# P03_Power.net
KiCad netlist of a schematic drawn in Altium Designer
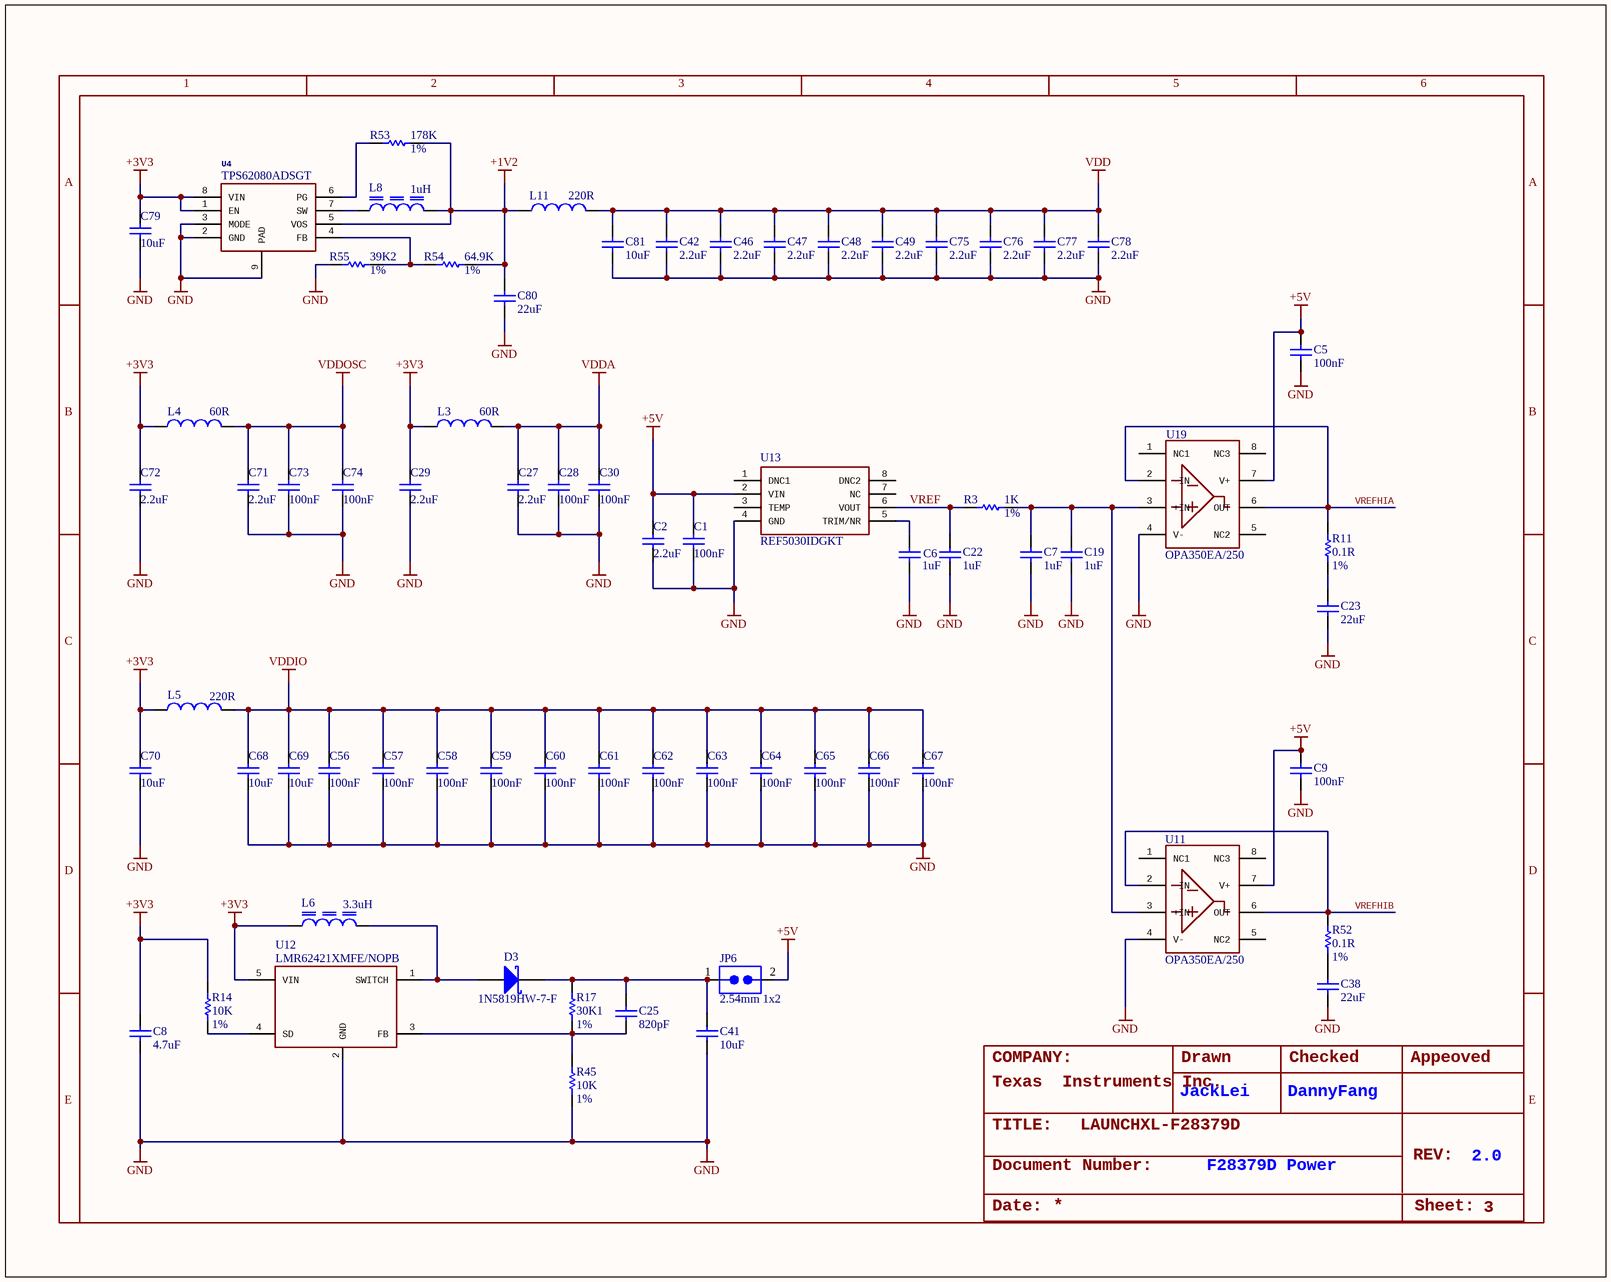
[diagram p0: P03_Power.SchDoc]

(export (version "E")
  (design (tool "Eeschema 10.0.6"))
  (components
    (comp (ref "C1")
      (value "100nF")
      (footprint "C0402")
      (description "CAP,100NF(0.1uf),+/-10%,X5R,10V,SMD0402")
      (fields
        (field (name "MANUFACTURER") "MURATA")
        (field (name "MANUFACTURER PART NUMBER") "GRM155R61A104KA01D")
      )
      (libsource (lib "Embest") (part "C"))
    )
    (comp (ref "C2")
      (value "2.2uF")
      (footprint "C0402")
      (description "CAP,2.2UF,+/-20%,X5R,6.3V,SMD0402")
      (fields
        (field (name "MANUFACTURER") "MURATA")
        (field (name "MANUFACTURER PART NUMBER") "GRM155R60J225ME15D")
      )
      (libsource (lib "Embest") (part "C"))
    )
    (comp (ref "C5")
      (value "100nF")
      (footprint "C0402")
      (description "CAP,100NF(0.1uf),+/-10%,X5R,10V,SMD0402")
      (fields
        (field (name "MANUFACTURER") "MURATA")
        (field (name "MANUFACTURER PART NUMBER") "GRM155R61A104KA01D")
      )
      (libsource (lib "Embest") (part "C"))
    )
    (comp (ref "C6")
      (value "1uF")
      (footprint "C0402")
      (description "CAP,1UF,+/-10%,X5R,6.3V,SMD0402")
      (fields
        (field (name "MANUFACTURER") "MURATA")
        (field (name "MANUFACTURER PART NUMBER") "GRM155R60J105KE19D")
      )
      (libsource (lib "Embest") (part "C"))
    )
    (comp (ref "C7")
      (value "1uF")
      (footprint "C0402")
      (description "CAP,1UF,+/-10%,X5R,6.3V,SMD0402")
      (fields
        (field (name "MANUFACTURER") "MURATA")
        (field (name "MANUFACTURER PART NUMBER") "GRM155R60J105KE19D")
      )
      (libsource (lib "Embest") (part "C"))
    )
    (comp (ref "C8")
      (value "4.7uF")
      (footprint "C0402")
      (description "CAP,4.7UF,+/-20%,X5R,6.3V,SMD0402 fix PN add D（20151023）")
      (fields
        (field (name "MANUFACTURER") "MURATA")
        (field (name "MANUFACTURER PART NUMBER") "GRM155R60J475ME47D")
      )
      (libsource (lib "Embest") (part "C"))
    )
    (comp (ref "C9")
      (value "100nF")
      (footprint "C0402")
      (description "CAP,100NF(0.1uf),+/-10%,X5R,10V,SMD0402")
      (fields
        (field (name "MANUFACTURER") "MURATA")
        (field (name "MANUFACTURER PART NUMBER") "GRM155R61A104KA01D")
      )
      (libsource (lib "Embest") (part "C"))
    )
    (comp (ref "C19")
      (value "1uF")
      (footprint "C0402")
      (description "CAP,1UF,+/-10%,X5R,6.3V,SMD0402")
      (fields
        (field (name "MANUFACTURER") "MURATA")
        (field (name "MANUFACTURER PART NUMBER") "GRM155R60J105KE19D")
      )
      (libsource (lib "Embest") (part "C"))
    )
    (comp (ref "C22")
      (value "1uF")
      (footprint "C0402")
      (description "CAP,1UF,+/-10%,X5R,6.3V,SMD0402")
      (fields
        (field (name "MANUFACTURER") "MURATA")
        (field (name "MANUFACTURER PART NUMBER") "GRM155R60J105KE19D")
      )
      (libsource (lib "Embest") (part "C"))
    )
    (comp (ref "C23")
      (value "22uF")
      (footprint "C0603")
      (description "CAP,22UF,+/-20%,X5R,6.3V,SMD0603")
      (fields
        (field (name "MANUFACTURER") "MURATA")
        (field (name "MANUFACTURER PART NUMBER") "GRM188R60J226MEA0D")
      )
      (libsource (lib "Embest") (part "C"))
    )
    (comp (ref "C25")
      (value "820pF")
      (footprint "C0402")
      (description "CAP,820PF,+/-5%,C0G,50V,SMD0402")
      (fields
        (field (name "MANUFACTURER") "MURATA")
        (field (name "MANUFACTURER PART NUMBER") "GRM1555C1H821JA01D")
      )
      (libsource (lib "Embest") (part "C"))
    )
    (comp (ref "C27")
      (value "2.2uF")
      (footprint "C0402")
      (description "CAP,2.2UF,+/-20%,X5R,6.3V,SMD0402")
      (fields
        (field (name "MANUFACTURER") "MURATA")
        (field (name "MANUFACTURER PART NUMBER") "GRM155R60J225ME15D")
      )
      (libsource (lib "Embest") (part "C"))
    )
    (comp (ref "C28")
      (value "100nF")
      (footprint "C0402")
      (description "CAP,100NF(0.1uf),+/-10%,X5R,10V,SMD0402")
      (fields
        (field (name "MANUFACTURER") "MURATA")
        (field (name "MANUFACTURER PART NUMBER") "GRM155R61A104KA01D")
      )
      (libsource (lib "Embest") (part "C"))
    )
    (comp (ref "C29")
      (value "2.2uF")
      (footprint "C0402")
      (description "CAP,2.2UF,+/-20%,X5R,6.3V,SMD0402")
      (fields
        (field (name "MANUFACTURER") "MURATA")
        (field (name "MANUFACTURER PART NUMBER") "GRM155R60J225ME15D")
      )
      (libsource (lib "Embest") (part "C"))
    )
    (comp (ref "C30")
      (value "100nF")
      (footprint "C0402")
      (description "CAP,100NF(0.1uf),+/-10%,X5R,10V,SMD0402")
      (fields
        (field (name "MANUFACTURER") "MURATA")
        (field (name "MANUFACTURER PART NUMBER") "GRM155R61A104KA01D")
      )
      (libsource (lib "Embest") (part "C"))
    )
    (comp (ref "C38")
      (value "22uF")
      (footprint "C0603")
      (description "CAP,22UF,+/-20%,X5R,6.3V,SMD0603")
      (fields
        (field (name "MANUFACTURER") "MURATA")
        (field (name "MANUFACTURER PART NUMBER") "GRM188R60J226MEA0D")
      )
      (libsource (lib "Embest") (part "C"))
    )
    (comp (ref "C41")
      (value "10uF")
      (footprint "C1210")
      (description "CAP,10UF,+/-10%,X7R,25V,SMD1210")
      (fields
        (field (name "MANUFACTURER") "MURATA")
        (field (name "MANUFACTURER PART NUMBER") "GRM32DR71E106KA12L")
      )
      (libsource (lib "Embest") (part "C"))
    )
    (comp (ref "C42")
      (value "2.2uF")
      (footprint "C0402")
      (description "CAP,2.2UF,+/-20%,X5R,6.3V,SMD0402")
      (fields
        (field (name "MANUFACTURER") "MURATA")
        (field (name "MANUFACTURER PART NUMBER") "GRM155R60J225ME15D")
      )
      (libsource (lib "Embest") (part "C"))
    )
    (comp (ref "C46")
      (value "2.2uF")
      (footprint "C0402")
      (description "CAP,2.2UF,+/-20%,X5R,6.3V,SMD0402")
      (fields
        (field (name "MANUFACTURER") "MURATA")
        (field (name "MANUFACTURER PART NUMBER") "GRM155R60J225ME15D")
      )
      (libsource (lib "Embest") (part "C"))
    )
    (comp (ref "C47")
      (value "2.2uF")
      (footprint "C0402")
      (description "CAP,2.2UF,+/-20%,X5R,6.3V,SMD0402")
      (fields
        (field (name "MANUFACTURER") "MURATA")
        (field (name "MANUFACTURER PART NUMBER") "GRM155R60J225ME15D")
      )
      (libsource (lib "Embest") (part "C"))
    )
    (comp (ref "C48")
      (value "2.2uF")
      (footprint "C0402")
      (description "CAP,2.2UF,+/-20%,X5R,6.3V,SMD0402")
      (fields
        (field (name "MANUFACTURER") "MURATA")
        (field (name "MANUFACTURER PART NUMBER") "GRM155R60J225ME15D")
      )
      (libsource (lib "Embest") (part "C"))
    )
    (comp (ref "C49")
      (value "2.2uF")
      (footprint "C0402")
      (description "CAP,2.2UF,+/-20%,X5R,6.3V,SMD0402")
      (fields
        (field (name "MANUFACTURER") "MURATA")
        (field (name "MANUFACTURER PART NUMBER") "GRM155R60J225ME15D")
      )
      (libsource (lib "Embest") (part "C"))
    )
    (comp (ref "C56")
      (value "100nF")
      (footprint "C0402")
      (description "CAP,100NF(0.1uf),+/-10%,X5R,10V,SMD0402")
      (fields
        (field (name "MANUFACTURER") "MURATA")
        (field (name "MANUFACTURER PART NUMBER") "GRM155R61A104KA01D")
      )
      (libsource (lib "Embest") (part "C"))
    )
    (comp (ref "C57")
      (value "100nF")
      (footprint "C0402")
      (description "CAP,100NF(0.1uf),+/-10%,X5R,10V,SMD0402")
      (fields
        (field (name "MANUFACTURER") "MURATA")
        (field (name "MANUFACTURER PART NUMBER") "GRM155R61A104KA01D")
      )
      (libsource (lib "Embest") (part "C"))
    )
    (comp (ref "C58")
      (value "100nF")
      (footprint "C0402")
      (description "CAP,100NF(0.1uf),+/-10%,X5R,10V,SMD0402")
      (fields
        (field (name "MANUFACTURER") "MURATA")
        (field (name "MANUFACTURER PART NUMBER") "GRM155R61A104KA01D")
      )
      (libsource (lib "Embest") (part "C"))
    )
    (comp (ref "C59")
      (value "100nF")
      (footprint "C0402")
      (description "CAP,100NF(0.1uf),+/-10%,X5R,10V,SMD0402")
      (fields
        (field (name "MANUFACTURER") "MURATA")
        (field (name "MANUFACTURER PART NUMBER") "GRM155R61A104KA01D")
      )
      (libsource (lib "Embest") (part "C"))
    )
    (comp (ref "C60")
      (value "100nF")
      (footprint "C0402")
      (description "CAP,100NF(0.1uf),+/-10%,X5R,10V,SMD0402")
      (fields
        (field (name "MANUFACTURER") "MURATA")
        (field (name "MANUFACTURER PART NUMBER") "GRM155R61A104KA01D")
      )
      (libsource (lib "Embest") (part "C"))
    )
    (comp (ref "C61")
      (value "100nF")
      (footprint "C0402")
      (description "CAP,100NF(0.1uf),+/-10%,X5R,10V,SMD0402")
      (fields
        (field (name "MANUFACTURER") "MURATA")
        (field (name "MANUFACTURER PART NUMBER") "GRM155R61A104KA01D")
      )
      (libsource (lib "Embest") (part "C"))
    )
    (comp (ref "C62")
      (value "100nF")
      (footprint "C0402")
      (description "CAP,100NF(0.1uf),+/-10%,X5R,10V,SMD0402")
      (fields
        (field (name "MANUFACTURER") "MURATA")
        (field (name "MANUFACTURER PART NUMBER") "GRM155R61A104KA01D")
      )
      (libsource (lib "Embest") (part "C"))
    )
    (comp (ref "C63")
      (value "100nF")
      (footprint "C0402")
      (description "CAP,100NF(0.1uf),+/-10%,X5R,10V,SMD0402")
      (fields
        (field (name "MANUFACTURER") "MURATA")
        (field (name "MANUFACTURER PART NUMBER") "GRM155R61A104KA01D")
      )
      (libsource (lib "Embest") (part "C"))
    )
    (comp (ref "C64")
      (value "100nF")
      (footprint "C0402")
      (description "CAP,100NF(0.1uf),+/-10%,X5R,10V,SMD0402")
      (fields
        (field (name "MANUFACTURER") "MURATA")
        (field (name "MANUFACTURER PART NUMBER") "GRM155R61A104KA01D")
      )
      (libsource (lib "Embest") (part "C"))
    )
    (comp (ref "C65")
      (value "100nF")
      (footprint "C0402")
      (description "CAP,100NF(0.1uf),+/-10%,X5R,10V,SMD0402")
      (fields
        (field (name "MANUFACTURER") "MURATA")
        (field (name "MANUFACTURER PART NUMBER") "GRM155R61A104KA01D")
      )
      (libsource (lib "Embest") (part "C"))
    )
    (comp (ref "C66")
      (value "100nF")
      (footprint "C0402")
      (description "CAP,100NF(0.1uf),+/-10%,X5R,10V,SMD0402")
      (fields
        (field (name "MANUFACTURER") "MURATA")
        (field (name "MANUFACTURER PART NUMBER") "GRM155R61A104KA01D")
      )
      (libsource (lib "Embest") (part "C"))
    )
    (comp (ref "C67")
      (value "100nF")
      (footprint "C0402")
      (description "CAP,100NF(0.1uf),+/-10%,X5R,10V,SMD0402")
      (fields
        (field (name "MANUFACTURER") "MURATA")
        (field (name "MANUFACTURER PART NUMBER") "GRM155R61A104KA01D")
      )
      (libsource (lib "Embest") (part "C"))
    )
    (comp (ref "C68")
      (value "10uF")
      (footprint "C0603")
      (description "CAP,10UF,+/-20%,X5R,6.3V,SMD0603")
      (fields
        (field (name "MANUFACTURER") "MURATA")
        (field (name "MANUFACTURER PART NUMBER") "GRM188R60J106ME47D")
      )
      (libsource (lib "Embest") (part "C"))
    )
    (comp (ref "C69")
      (value "10uF")
      (footprint "C0603")
      (description "CAP,10UF,+/-20%,X5R,6.3V,SMD0603")
      (fields
        (field (name "MANUFACTURER") "MURATA")
        (field (name "MANUFACTURER PART NUMBER") "GRM188R60J106ME47D")
      )
      (libsource (lib "Embest") (part "C"))
    )
    (comp (ref "C70")
      (value "10uF")
      (footprint "C0603")
      (description "CAP,10UF,+/-20%,X5R,6.3V,SMD0603")
      (fields
        (field (name "MANUFACTURER") "MURATA")
        (field (name "MANUFACTURER PART NUMBER") "GRM188R60J106ME47D")
      )
      (libsource (lib "Embest") (part "C"))
    )
    (comp (ref "C71")
      (value "2.2uF")
      (footprint "C0402")
      (description "CAP,2.2UF,+/-20%,X5R,6.3V,SMD0402")
      (fields
        (field (name "MANUFACTURER") "MURATA")
        (field (name "MANUFACTURER PART NUMBER") "GRM155R60J225ME15D")
      )
      (libsource (lib "Embest") (part "C"))
    )
    (comp (ref "C72")
      (value "2.2uF")
      (footprint "C0402")
      (description "CAP,2.2UF,+/-20%,X5R,6.3V,SMD0402")
      (fields
        (field (name "MANUFACTURER") "MURATA")
        (field (name "MANUFACTURER PART NUMBER") "GRM155R60J225ME15D")
      )
      (libsource (lib "Embest") (part "C"))
    )
    (comp (ref "C73")
      (value "100nF")
      (footprint "C0402")
      (description "CAP,100NF(0.1uf),+/-10%,X5R,10V,SMD0402")
      (fields
        (field (name "MANUFACTURER") "MURATA")
        (field (name "MANUFACTURER PART NUMBER") "GRM155R61A104KA01D")
      )
      (libsource (lib "Embest") (part "C"))
    )
    (comp (ref "C74")
      (value "100nF")
      (footprint "C0402")
      (description "CAP,100NF(0.1uf),+/-10%,X5R,10V,SMD0402")
      (fields
        (field (name "MANUFACTURER") "MURATA")
        (field (name "MANUFACTURER PART NUMBER") "GRM155R61A104KA01D")
      )
      (libsource (lib "Embest") (part "C"))
    )
    (comp (ref "C75")
      (value "2.2uF")
      (footprint "C0402")
      (description "CAP,2.2UF,+/-20%,X5R,6.3V,SMD0402")
      (fields
        (field (name "MANUFACTURER") "MURATA")
        (field (name "MANUFACTURER PART NUMBER") "GRM155R60J225ME15D")
      )
      (libsource (lib "Embest") (part "C"))
    )
    (comp (ref "C76")
      (value "2.2uF")
      (footprint "C0402")
      (description "CAP,2.2UF,+/-20%,X5R,6.3V,SMD0402")
      (fields
        (field (name "MANUFACTURER") "MURATA")
        (field (name "MANUFACTURER PART NUMBER") "GRM155R60J225ME15D")
      )
      (libsource (lib "Embest") (part "C"))
    )
    (comp (ref "C77")
      (value "2.2uF")
      (footprint "C0402")
      (description "CAP,2.2UF,+/-20%,X5R,6.3V,SMD0402")
      (fields
        (field (name "MANUFACTURER") "MURATA")
        (field (name "MANUFACTURER PART NUMBER") "GRM155R60J225ME15D")
      )
      (libsource (lib "Embest") (part "C"))
    )
    (comp (ref "C78")
      (value "2.2uF")
      (footprint "C0402")
      (description "CAP,2.2UF,+/-20%,X5R,6.3V,SMD0402")
      (fields
        (field (name "MANUFACTURER") "MURATA")
        (field (name "MANUFACTURER PART NUMBER") "GRM155R60J225ME15D")
      )
      (libsource (lib "Embest") (part "C"))
    )
    (comp (ref "C79")
      (value "10uF")
      (footprint "C0603")
      (description "CAP,10UF,+/-20%,X5R,6.3V,SMD0603")
      (fields
        (field (name "MANUFACTURER") "MURATA")
        (field (name "MANUFACTURER PART NUMBER") "GRM188R60J106ME47D")
      )
      (libsource (lib "Embest") (part "C"))
    )
    (comp (ref "C80")
      (value "22uF")
      (footprint "C0603")
      (description "CAP,22UF,+/-20%,X5R,6.3V,SMD0603")
      (fields
        (field (name "MANUFACTURER") "MURATA")
        (field (name "MANUFACTURER PART NUMBER") "GRM188R60J226MEA0D")
      )
      (libsource (lib "Embest") (part "C"))
    )
    (comp (ref "C81")
      (value "10uF")
      (footprint "C0603")
      (description "CAP,10UF,+/-20%,X5R,6.3V,SMD0603")
      (fields
        (field (name "MANUFACTURER") "MURATA")
        (field (name "MANUFACTURER PART NUMBER") "GRM188R60J106ME47D")
      )
      (libsource (lib "Embest") (part "C"))
    )
    (comp (ref "D3")
      (value "1N5819HW-7-F")
      (footprint "SOD-123")
      (description "Diode,Schottky Diode,1N5819HW-7-F,40V,1A,SOD-123,SMD,-65~125,TR")
      (fields (field (name "MANUFACTURER") "DIODES"))
      (libsource (lib "Embest") (part "DIODE SCHOTTKY"))
    )
    (comp (ref "JP6")
      (value "2.54mm 1x2")
      (footprint "HDRV2W64P254_1X2_508X250X850P")
      (fields
        (field (name "MANUFACTURER") "CHIN-BAN")
        (field (name "MANUFACTURER PART NUMBER") "P6E02A-602530-B1")
      )
      (libsource (lib "Embest") (part "SIP2"))
    )
    (comp (ref "L3")
      (value "60R")
      (footprint "L0402")
      (description "Ferrite Bead,60ohm@100MHz,+/-25%,1700mA,0.06ohm,SMD0402")
      (fields
        (field (name "MANUFACTURER") "MURATA")
        (field (name "MANUFACTURER PART NUMBER") "BLM15PD600SN1D")
      )
      (libsource (lib "Embest") (part "FB"))
    )
    (comp (ref "L4")
      (value "60R")
      (footprint "L0402")
      (description "Ferrite Bead,60ohm@100MHz,+/-25%,1700mA,0.06ohm,SMD0402")
      (fields
        (field (name "MANUFACTURER") "MURATA")
        (field (name "MANUFACTURER PART NUMBER") "BLM15PD600SN1D")
      )
      (libsource (lib "Embest") (part "FB"))
    )
    (comp (ref "L5")
      (value "220R")
      (footprint "L0402")
      (description "FERRITE BEAD 220 OHM 0402,+/-25%")
      (fields
        (field (name "MANUFACTURER") "Taiyo Yuden")
        (field (name "MANUFACTURER PART NUMBER") "BKP1005EM221-T")
      )
      (libsource (lib "Embest") (part "FB"))
    )
    (comp (ref "L6")
      (value "3.3uH")
      (footprint "INDC380X380X165N")
      (description "Power Inductor,Magnetic shielded,3.3uH,1.4A,0.085ohm,3.8X3.8X1.6mm,SMD")
      (fields
        (field (name "MANUFACTURER") "SUMIDA")
        (field (name "MANUFACTURER PART NUMBER") "CDRH3D16/HPNP-3R3NC")
      )
      (libsource (lib "Embest") (part "L"))
    )
    (comp (ref "L8")
      (value "1uH")
      (footprint "INDC3030X12N")
      (description "FIXED IND 1UH 1.62A 40 MOHM SMD,+/-30%")
      (fields
        (field (name "MANUFACTURER") "MURATA")
        (field (name "MANUFACTURER PART NUMBER") "LQH3NPN1R0NJ0L")
      )
      (libsource (lib "Embest") (part "L"))
    )
    (comp (ref "L11")
      (value "220R")
      (footprint "L0402")
      (description "FERRITE BEAD 220 OHM 0402,+/-25%")
      (fields
        (field (name "MANUFACTURER") "Taiyo Yuden")
        (field (name "MANUFACTURER PART NUMBER") "BKP1005EM221-T")
      )
      (libsource (lib "Embest") (part "FB"))
    )
    (comp (ref "R3")
      (value "1K")
      (footprint "R0402")
      (description "RES,1K,+/-1%,1/16W,SMD0402")
      (fields
        (field (name "RATING") "1%")
        (field (name "MANUFACTURER") "YAGEO")
        (field (name "MANUFACTURER PART NUMBER") "RC0402FR-071KL")
      )
      (libsource (lib "Embest") (part "R"))
    )
    (comp (ref "R11")
      (value "0.1R")
      (footprint "R0603")
      (description "RES,0R1,+/-1%,1/10W,SMD0603")
      (fields
        (field (name "RATING") "1%")
        (field (name "MANUFACTURER") "YAGEO")
        (field (name "MANUFACTURER PART NUMBER") "RL0603FR-070R1L")
      )
      (libsource (lib "Embest") (part "R"))
    )
    (comp (ref "R14")
      (value "10K")
      (footprint "R0402")
      (description "RES,10K,+/-1%,1/16W,SMD0402")
      (fields
        (field (name "RATING") "1%")
        (field (name "MANUFACTURER") "YAGEO")
        (field (name "MANUFACTURER PART NUMBER") "RC0402FR-0710KL")
      )
      (libsource (lib "Embest") (part "R"))
    )
    (comp (ref "R17")
      (value "30K1")
      (footprint "R0402")
      (description "RES,30K1,+/-1%,1/16W,SMD0402")
      (fields
        (field (name "RATING") "1%")
        (field (name "MANUFACTURER") "YAGEO")
        (field (name "MANUFACTURER PART NUMBER") "RC0402FR-0730K1L")
      )
      (libsource (lib "Embest") (part "R"))
    )
    (comp (ref "R45")
      (value "10K")
      (footprint "R0402")
      (description "RES,10K,+/-1%,1/16W,SMD0402")
      (fields
        (field (name "RATING") "1%")
        (field (name "MANUFACTURER") "YAGEO")
        (field (name "MANUFACTURER PART NUMBER") "RC0402FR-0710KL")
      )
      (libsource (lib "Embest") (part "R"))
    )
    (comp (ref "R52")
      (value "0.1R")
      (footprint "R0603")
      (description "RES,0R1,+/-1%,1/10W,SMD0603")
      (fields
        (field (name "RATING") "1%")
        (field (name "MANUFACTURER") "YAGEO")
        (field (name "MANUFACTURER PART NUMBER") "RL0603FR-070R1L")
      )
      (libsource (lib "Embest") (part "R"))
    )
    (comp (ref "R53")
      (value "178K")
      (footprint "R0402")
      (description "RES, 178K OHM, 1%, 1/10W, SMD0402")
      (fields
        (field (name "RATING") "1%")
        (field (name "MANUFACTURER") "PANASONIC")
        (field (name "MANUFACTURER PART NUMBER") "ERJ-2RKF1783X")
      )
      (libsource (lib "Embest") (part "R"))
    )
    (comp (ref "R54")
      (value "64.9K")
      (footprint "R0402")
      (description "RES, 64.9K OHM, 1%, 1/10W, SMD0402")
      (fields
        (field (name "RATING") "1%")
        (field (name "MANUFACTURER") "PANASONIC")
        (field (name "MANUFACTURER PART NUMBER") "ERJ-2RKF6492X")
      )
      (libsource (lib "Embest") (part "R"))
    )
    (comp (ref "R55")
      (value "39K2")
      (footprint "R0402")
      (description "RES,39K2,+/-1%,1/16W,SMD0402")
      (fields
        (field (name "RATING") "1%")
        (field (name "MANUFACTURER") "YAGEO")
        (field (name "MANUFACTURER PART NUMBER") "RC0402FR-0739K2L")
      )
      (libsource (lib "Embest") (part "R"))
    )
    (comp (ref "U4")
      (value "TPS62080ADSGT")
      (footprint "WSON50P200X80_HS-9N")
      (description "IC REG BUCK SYNC ADJ 1.2A 8WSON")
      (fields (field (name "MANUFACTURER") "TI"))
      (libsource (lib "Embest") (part "TPS62080"))
    )
    (comp (ref "U11")
      (value "OPA350EA/250")
      (footprint "VSSOP65P490X110-8N")
      (description "IC OPAMP GP 38MHZ RRO 8VSSOP T/R")
      (fields (field (name "MANUFACTURER") "TI"))
      (libsource (lib "Embest") (part "OPA350"))
    )
    (comp (ref "U12")
      (value "LMR62421XMFE/NOPB")
      (footprint "SOT23-5")
      (description "Conv DC-DC Single Step Up 2.7V to 5.5V 5-Pin SOT-23 T/R ,CUSTOMER SUPPLY")
      (fields (field (name "MANUFACTURER") "TI"))
      (libsource (lib "Embest") (part "LMR62421XMFE/NOPB"))
    )
    (comp (ref "U13")
      (value "REF5030IDGKT")
      (footprint "VSSOP65P490X110-8N")
      (description "IC ，V-Ref Precision 3V 10mA 8-Pin VSSOP T/R")
      (fields (field (name "MANUFACTURER") "TI"))
      (libsource (lib "Embest") (part "REF5030IDGKT"))
    )
    (comp (ref "U19")
      (value "OPA350EA/250")
      (footprint "VSSOP65P490X110-8N")
      (description "IC OPAMP GP 38MHZ RRO 8VSSOP T/R")
      (fields (field (name "MANUFACTURER") "TI"))
      (libsource (lib "Embest") (part "OPA350"))
    )
  )
  (nets
    (net (code "1") (name "+1V2") (class "Default")
      (node (ref "C80") (pin "2") (pinfunction "2_2") (pintype "passive"))
      (node (ref "L11") (pin "1") (pinfunction "1_1") (pintype "passive"))
      (node (ref "L8") (pin "2") (pinfunction "2_2") (pintype "passive"))
      (node (ref "R53") (pin "2") (pinfunction "2_2") (pintype "passive"))
      (node (ref "R54") (pin "2") (pinfunction "2_2") (pintype "passive"))
      (node (ref "U4") (pin "5") (pinfunction "VOS_5") (pintype "passive"))
    )
    (net (code "2") (name "+3V3") (class "Default")
      (node (ref "C29") (pin "2") (pinfunction "2_2") (pintype "passive"))
      (node (ref "C70") (pin "2") (pinfunction "2_2") (pintype "passive"))
      (node (ref "C72") (pin "2") (pinfunction "2_2") (pintype "passive"))
      (node (ref "C79") (pin "2") (pinfunction "2_2") (pintype "passive"))
      (node (ref "C8") (pin "2") (pinfunction "2_2") (pintype "passive"))
      (node (ref "L3") (pin "1") (pinfunction "1_1") (pintype "passive"))
      (node (ref "L4") (pin "1") (pinfunction "1_1") (pintype "passive"))
      (node (ref "L5") (pin "1") (pinfunction "1_1") (pintype "passive"))
      (node (ref "L6") (pin "1") (pinfunction "1_1") (pintype "passive"))
      (node (ref "R14") (pin "1") (pinfunction "1_1") (pintype "passive"))
      (node (ref "U12") (pin "5") (pinfunction "VIN_5") (pintype "passive"))
      (node (ref "U4") (pin "1") (pinfunction "EN_1") (pintype "passive"))
      (node (ref "U4") (pin "8") (pinfunction "VIN_8") (pintype "passive"))
    )
    (net (code "3") (name "+5V") (class "Default")
      (node (ref "C1") (pin "2") (pinfunction "2_2") (pintype "passive"))
      (node (ref "C2") (pin "2") (pinfunction "2_2") (pintype "passive"))
      (node (ref "C5") (pin "2") (pinfunction "2_2") (pintype "passive"))
      (node (ref "C9") (pin "2") (pinfunction "2_2") (pintype "passive"))
      (node (ref "JP6") (pin "2") (pinfunction "2_2") (pintype "passive"))
      (node (ref "U11") (pin "7") (pinfunction "V+_7") (pintype "passive"))
      (node (ref "U13") (pin "2") (pinfunction "VIN_2") (pintype "passive"))
      (node (ref "U19") (pin "7") (pinfunction "V+_7") (pintype "passive"))
    )
    (net (code "4") (name "/VREF") (class "Default")
      (node (ref "C22") (pin "2") (pinfunction "2_2") (pintype "passive"))
      (node (ref "R3") (pin "1") (pinfunction "1_1") (pintype "passive"))
      (node (ref "U13") (pin "6") (pinfunction "VOUT_6") (pintype "passive"))
    )
    (net (code "5") (name "/VREFHIA") (class "Default")
      (node (ref "R11") (pin "2") (pinfunction "2_2") (pintype "passive"))
      (node (ref "U19") (pin "2") (pinfunction "-IN_2") (pintype "passive"))
      (node (ref "U19") (pin "6") (pinfunction "OUT_6") (pintype "passive"))
    )
    (net (code "6") (name "/VREFHIB") (class "Default")
      (node (ref "R52") (pin "2") (pinfunction "2_2") (pintype "passive"))
      (node (ref "U11") (pin "2") (pinfunction "-IN_2") (pintype "passive"))
      (node (ref "U11") (pin "6") (pinfunction "OUT_6") (pintype "passive"))
    )
    (net (code "7") (name "GND") (class "Default")
      (node (ref "C1") (pin "1") (pinfunction "1_1") (pintype "passive"))
      (node (ref "C19") (pin "1") (pinfunction "1_1") (pintype "passive"))
      (node (ref "C2") (pin "1") (pinfunction "1_1") (pintype "passive"))
      (node (ref "C22") (pin "1") (pinfunction "1_1") (pintype "passive"))
      (node (ref "C23") (pin "1") (pinfunction "1_1") (pintype "passive"))
      (node (ref "C27") (pin "1") (pinfunction "1_1") (pintype "passive"))
      (node (ref "C28") (pin "1") (pinfunction "1_1") (pintype "passive"))
      (node (ref "C29") (pin "1") (pinfunction "1_1") (pintype "passive"))
      (node (ref "C30") (pin "1") (pinfunction "1_1") (pintype "passive"))
      (node (ref "C38") (pin "1") (pinfunction "1_1") (pintype "passive"))
      (node (ref "C41") (pin "2") (pinfunction "2_2") (pintype "passive"))
      (node (ref "C42") (pin "1") (pinfunction "1_1") (pintype "passive"))
      (node (ref "C46") (pin "1") (pinfunction "1_1") (pintype "passive"))
      (node (ref "C47") (pin "1") (pinfunction "1_1") (pintype "passive"))
      (node (ref "C48") (pin "1") (pinfunction "1_1") (pintype "passive"))
      (node (ref "C49") (pin "1") (pinfunction "1_1") (pintype "passive"))
      (node (ref "C5") (pin "1") (pinfunction "1_1") (pintype "passive"))
      (node (ref "C56") (pin "1") (pinfunction "1_1") (pintype "passive"))
      (node (ref "C57") (pin "2") (pinfunction "2_2") (pintype "passive"))
      (node (ref "C58") (pin "1") (pinfunction "1_1") (pintype "passive"))
      (node (ref "C59") (pin "1") (pinfunction "1_1") (pintype "passive"))
      (node (ref "C6") (pin "1") (pinfunction "1_1") (pintype "passive"))
      (node (ref "C60") (pin "1") (pinfunction "1_1") (pintype "passive"))
      (node (ref "C61") (pin "1") (pinfunction "1_1") (pintype "passive"))
      (node (ref "C62") (pin "1") (pinfunction "1_1") (pintype "passive"))
      (node (ref "C63") (pin "1") (pinfunction "1_1") (pintype "passive"))
      (node (ref "C64") (pin "1") (pinfunction "1_1") (pintype "passive"))
      (node (ref "C65") (pin "1") (pinfunction "1_1") (pintype "passive"))
      (node (ref "C66") (pin "1") (pinfunction "1_1") (pintype "passive"))
      (node (ref "C67") (pin "1") (pinfunction "1_1") (pintype "passive"))
      (node (ref "C68") (pin "1") (pinfunction "1_1") (pintype "passive"))
      (node (ref "C69") (pin "1") (pinfunction "1_1") (pintype "passive"))
      (node (ref "C7") (pin "1") (pinfunction "1_1") (pintype "passive"))
      (node (ref "C70") (pin "1") (pinfunction "1_1") (pintype "passive"))
      (node (ref "C71") (pin "1") (pinfunction "1_1") (pintype "passive"))
      (node (ref "C72") (pin "1") (pinfunction "1_1") (pintype "passive"))
      (node (ref "C73") (pin "1") (pinfunction "1_1") (pintype "passive"))
      (node (ref "C74") (pin "1") (pinfunction "1_1") (pintype "passive"))
      (node (ref "C75") (pin "1") (pinfunction "1_1") (pintype "passive"))
      (node (ref "C76") (pin "1") (pinfunction "1_1") (pintype "passive"))
      (node (ref "C77") (pin "1") (pinfunction "1_1") (pintype "passive"))
      (node (ref "C78") (pin "1") (pinfunction "1_1") (pintype "passive"))
      (node (ref "C79") (pin "1") (pinfunction "1_1") (pintype "passive"))
      (node (ref "C8") (pin "1") (pinfunction "1_1") (pintype "passive"))
      (node (ref "C80") (pin "1") (pinfunction "1_1") (pintype "passive"))
      (node (ref "C81") (pin "1") (pinfunction "1_1") (pintype "passive"))
      (node (ref "C9") (pin "1") (pinfunction "1_1") (pintype "passive"))
      (node (ref "R45") (pin "2") (pinfunction "2_2") (pintype "passive"))
      (node (ref "R55") (pin "1") (pinfunction "1_1") (pintype "passive"))
      (node (ref "U11") (pin "4") (pinfunction "V-_4") (pintype "passive"))
      (node (ref "U12") (pin "2") (pinfunction "GND_2") (pintype "passive"))
      (node (ref "U13") (pin "4") (pinfunction "GND_4") (pintype "passive"))
      (node (ref "U19") (pin "4") (pinfunction "V-_4") (pintype "passive"))
      (node (ref "U4") (pin "2") (pinfunction "GND_2") (pintype "passive"))
      (node (ref "U4") (pin "3") (pinfunction "MODE_3") (pintype "passive"))
      (node (ref "U4") (pin "9") (pinfunction "PAD_9") (pintype "passive"))
    )
    (net (code "8") (name "Net-(C23-Pad2)") (class "Default")
      (node (ref "C23") (pin "2") (pinfunction "2_2") (pintype "passive"))
      (node (ref "R11") (pin "1") (pinfunction "1_1") (pintype "passive"))
    )
    (net (code "9") (name "Net-(C25-Pad2)") (class "Default")
      (node (ref "C25") (pin "2") (pinfunction "2_2") (pintype "passive"))
      (node (ref "C41") (pin "1") (pinfunction "1_1") (pintype "passive"))
      (node (ref "D3") (pin "1") (pinfunction "1_1") (pintype "passive"))
      (node (ref "JP6") (pin "1") (pinfunction "1_1") (pintype "passive"))
      (node (ref "R17") (pin "1") (pinfunction "1_1") (pintype "passive"))
    )
    (net (code "10") (name "Net-(C38-Pad2)") (class "Default")
      (node (ref "C38") (pin "2") (pinfunction "2_2") (pintype "passive"))
      (node (ref "R52") (pin "1") (pinfunction "1_1") (pintype "passive"))
    )
    (net (code "11") (name "Net-(U4-FB)") (class "Default")
      (node (ref "R54") (pin "1") (pinfunction "1_1") (pintype "passive"))
      (node (ref "R55") (pin "2") (pinfunction "2_2") (pintype "passive"))
      (node (ref "U4") (pin "4") (pinfunction "FB_4") (pintype "passive"))
    )
    (net (code "12") (name "Net-(U4-PG)") (class "Default")
      (node (ref "R53") (pin "1") (pinfunction "1_1") (pintype "passive"))
      (node (ref "U4") (pin "6") (pinfunction "PG_6") (pintype "passive"))
    )
    (net (code "13") (name "Net-(U4-SW)") (class "Default")
      (node (ref "L8") (pin "1") (pinfunction "1_1") (pintype "passive"))
      (node (ref "U4") (pin "7") (pinfunction "SW_7") (pintype "passive"))
    )
    (net (code "14") (name "Net-(U11-+IN)") (class "Default")
      (node (ref "C19") (pin "2") (pinfunction "2_2") (pintype "passive"))
      (node (ref "C7") (pin "2") (pinfunction "2_2") (pintype "passive"))
      (node (ref "R3") (pin "2") (pinfunction "2_2") (pintype "passive"))
      (node (ref "U11") (pin "3") (pinfunction "+IN_3") (pintype "passive"))
      (node (ref "U19") (pin "3") (pinfunction "+IN_3") (pintype "passive"))
    )
    (net (code "15") (name "Net-(U12-FB)") (class "Default")
      (node (ref "C25") (pin "1") (pinfunction "1_1") (pintype "passive"))
      (node (ref "R17") (pin "2") (pinfunction "2_2") (pintype "passive"))
      (node (ref "R45") (pin "1") (pinfunction "1_1") (pintype "passive"))
      (node (ref "U12") (pin "3") (pinfunction "FB_3") (pintype "passive"))
    )
    (net (code "16") (name "Net-(U12-SD)") (class "Default")
      (node (ref "R14") (pin "2") (pinfunction "2_2") (pintype "passive"))
      (node (ref "U12") (pin "4") (pinfunction "SD_4") (pintype "passive"))
    )
    (net (code "17") (name "Net-(U12-SWITCH)") (class "Default")
      (node (ref "D3") (pin "2") (pinfunction "2_2") (pintype "passive"))
      (node (ref "L6") (pin "2") (pinfunction "2_2") (pintype "passive"))
      (node (ref "U12") (pin "1") (pinfunction "SWITCH_1") (pintype "passive"))
    )
    (net (code "18") (name "Net-(U13-TRIM{slash}NR)") (class "Default")
      (node (ref "C6") (pin "2") (pinfunction "2_2") (pintype "passive"))
      (node (ref "U13") (pin "5") (pinfunction "TRIM/NR_5") (pintype "passive"))
    )
    (net (code "19") (name "VDD") (class "Default")
      (node (ref "C42") (pin "2") (pinfunction "2_2") (pintype "passive"))
      (node (ref "C46") (pin "2") (pinfunction "2_2") (pintype "passive"))
      (node (ref "C47") (pin "2") (pinfunction "2_2") (pintype "passive"))
      (node (ref "C48") (pin "2") (pinfunction "2_2") (pintype "passive"))
      (node (ref "C49") (pin "2") (pinfunction "2_2") (pintype "passive"))
      (node (ref "C75") (pin "2") (pinfunction "2_2") (pintype "passive"))
      (node (ref "C76") (pin "2") (pinfunction "2_2") (pintype "passive"))
      (node (ref "C77") (pin "2") (pinfunction "2_2") (pintype "passive"))
      (node (ref "C78") (pin "2") (pinfunction "2_2") (pintype "passive"))
      (node (ref "C81") (pin "2") (pinfunction "2_2") (pintype "passive"))
      (node (ref "L11") (pin "2") (pinfunction "2_2") (pintype "passive"))
    )
    (net (code "20") (name "VDDA") (class "Default")
      (node (ref "C27") (pin "2") (pinfunction "2_2") (pintype "passive"))
      (node (ref "C28") (pin "2") (pinfunction "2_2") (pintype "passive"))
      (node (ref "C30") (pin "2") (pinfunction "2_2") (pintype "passive"))
      (node (ref "L3") (pin "2") (pinfunction "2_2") (pintype "passive"))
    )
    (net (code "21") (name "VDDIO") (class "Default")
      (node (ref "C56") (pin "2") (pinfunction "2_2") (pintype "passive"))
      (node (ref "C57") (pin "1") (pinfunction "1_1") (pintype "passive"))
      (node (ref "C58") (pin "2") (pinfunction "2_2") (pintype "passive"))
      (node (ref "C59") (pin "2") (pinfunction "2_2") (pintype "passive"))
      (node (ref "C60") (pin "2") (pinfunction "2_2") (pintype "passive"))
      (node (ref "C61") (pin "2") (pinfunction "2_2") (pintype "passive"))
      (node (ref "C62") (pin "2") (pinfunction "2_2") (pintype "passive"))
      (node (ref "C63") (pin "2") (pinfunction "2_2") (pintype "passive"))
      (node (ref "C64") (pin "2") (pinfunction "2_2") (pintype "passive"))
      (node (ref "C65") (pin "2") (pinfunction "2_2") (pintype "passive"))
      (node (ref "C66") (pin "2") (pinfunction "2_2") (pintype "passive"))
      (node (ref "C67") (pin "2") (pinfunction "2_2") (pintype "passive"))
      (node (ref "C68") (pin "2") (pinfunction "2_2") (pintype "passive"))
      (node (ref "C69") (pin "2") (pinfunction "2_2") (pintype "passive"))
      (node (ref "L5") (pin "2") (pinfunction "2_2") (pintype "passive"))
    )
    (net (code "22") (name "VDDOSC") (class "Default")
      (node (ref "C71") (pin "2") (pinfunction "2_2") (pintype "passive"))
      (node (ref "C73") (pin "2") (pinfunction "2_2") (pintype "passive"))
      (node (ref "C74") (pin "2") (pinfunction "2_2") (pintype "passive"))
      (node (ref "L4") (pin "2") (pinfunction "2_2") (pintype "passive"))
    )
    (net (code "23") (name "unconnected-(U11-NC1-Pad1)") (class "Default")
      (node (ref "U11") (pin "1") (pinfunction "NC1_1") (pintype "passive"))
    )
    (net (code "24") (name "unconnected-(U11-NC2-Pad5)") (class "Default")
      (node (ref "U11") (pin "5") (pinfunction "NC2_5") (pintype "passive"))
    )
    (net (code "25") (name "unconnected-(U11-NC3-Pad8)") (class "Default")
      (node (ref "U11") (pin "8") (pinfunction "NC3_8") (pintype "passive"))
    )
    (net (code "26") (name "unconnected-(U13-DNC1-Pad1)") (class "Default")
      (node (ref "U13") (pin "1") (pinfunction "DNC1_1") (pintype "passive"))
    )
    (net (code "27") (name "unconnected-(U13-DNC2-Pad8)") (class "Default")
      (node (ref "U13") (pin "8") (pinfunction "DNC2_8") (pintype "passive"))
    )
    (net (code "28") (name "unconnected-(U13-NC-Pad7)") (class "Default")
      (node (ref "U13") (pin "7") (pinfunction "NC_7") (pintype "passive"))
    )
    (net (code "29") (name "unconnected-(U13-TEMP-Pad3)") (class "Default")
      (node (ref "U13") (pin "3") (pinfunction "TEMP_3") (pintype "passive"))
    )
    (net (code "30") (name "unconnected-(U19-NC1-Pad1)") (class "Default")
      (node (ref "U19") (pin "1") (pinfunction "NC1_1") (pintype "passive"))
    )
    (net (code "31") (name "unconnected-(U19-NC2-Pad5)") (class "Default")
      (node (ref "U19") (pin "5") (pinfunction "NC2_5") (pintype "passive"))
    )
    (net (code "32") (name "unconnected-(U19-NC3-Pad8)") (class "Default")
      (node (ref "U19") (pin "8") (pinfunction "NC3_8") (pintype "passive"))
    )
  )
)
